# RP2350_QSPI.net
KiCad netlist of a schematic drawn in Altium Designer
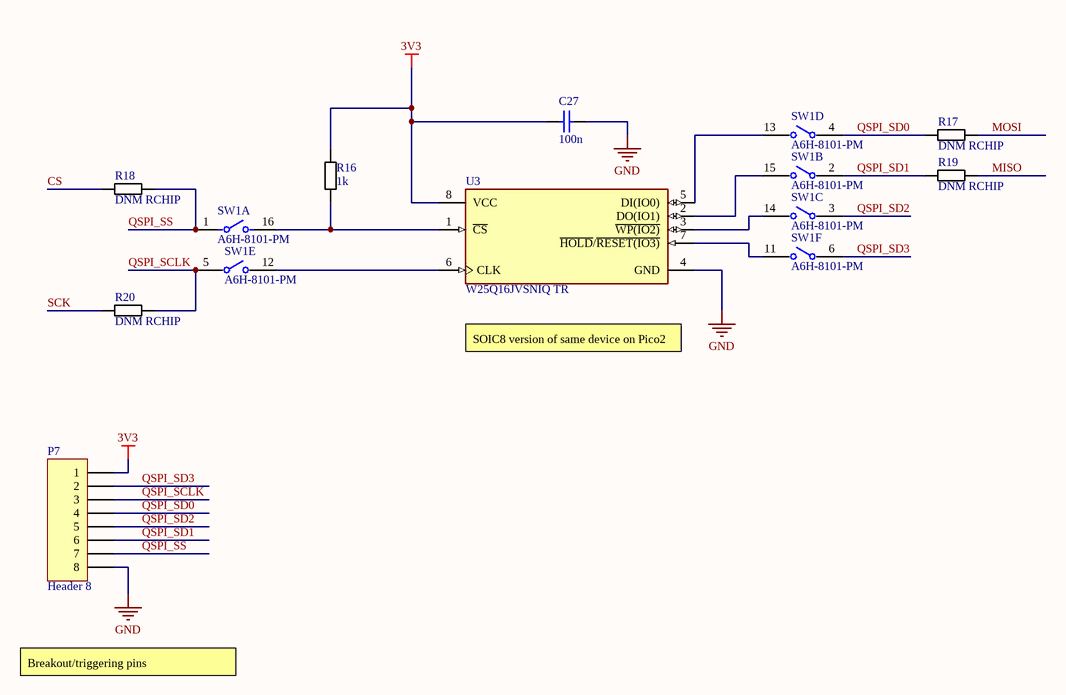
[diagram p0: RP2350_QSPI.SchDoc]

(export (version "E")
  (design (tool "Eeschema 10.0.6"))
  (components
    (comp (ref "C27")
      (value "100n")
      (footprint "CAPC0603_M")
      (description "100n, 0603")
      (fields (field (name "PART NUMBER") "CCHIP-100n-0603"))
      (libsource (lib "NewAE_AltiumLib") (part "CAP"))
    )
    (comp (ref "P7")
      (value "Header 8")
      (footprint "HDR1X8")
      (description "Header, 8-Pin")
      (fields (field (name "PUBLISHER") "Altium Limited"))
      (libsource (lib "Miscellaneous Connectors") (part "Header 8"))
    )
    (comp (ref "R16")
      (value "1k")
      (footprint "RESC1608X55N")
      (description "1k res, 0603, 1%, 1/10W")
      (fields (field (name "PART NUMBER") "RCHIP-1K-0603") (field (name "TOLERANCE") "1%"))
      (libsource (lib "") (part "RES-EU_1"))
    )
    (comp (ref "R17")
      (value "DNM RCHIP")
      (footprint "RESC1608X55N")
      (description "Do Not Mount Resistor")
      (fields (field (name "PART NUMBER") "RCHIP-DNM-0603"))
      (libsource (lib "NewAE_AltiumLib") (part "RES-EU"))
    )
    (comp (ref "R18")
      (value "DNM RCHIP")
      (footprint "RESC1608X55N")
      (description "Do Not Mount Resistor")
      (fields (field (name "PART NUMBER") "RCHIP-DNM-0603"))
      (libsource (lib "NewAE_AltiumLib") (part "RES-EU"))
    )
    (comp (ref "R19")
      (value "DNM RCHIP")
      (footprint "RESC1608X55N")
      (description "Do Not Mount Resistor")
      (fields (field (name "PART NUMBER") "RCHIP-DNM-0603"))
      (libsource (lib "NewAE_AltiumLib") (part "RES-EU"))
    )
    (comp (ref "R20")
      (value "DNM RCHIP")
      (footprint "RESC1608X55N")
      (description "Do Not Mount Resistor")
      (fields (field (name "PART NUMBER") "RCHIP-DNM-0603"))
      (libsource (lib "NewAE_AltiumLib") (part "RES-EU"))
    )
    (comp (ref "SW1")
      (value "A6H-8101-PM")
      (footprint "FP-A6H-8101-PM-MFG")
      (description "SWITCH SLIDE DIP SPST 25MA 24V")
      (libsource (lib "Altium Content Vault") (part "b1c630a2f26d6f55c46b66680387f8a"))
    )
    (comp (ref "U3")
      (value "W25Q16JVSNIQ TR")
      (footprint "FP-W25Q16JVSNIQ_TR-IPC_A")
      (description "IC FLASH 16MBIT SPI/QUAD 8SOIC")
      (libsource (lib "Altium Content Vault") (part "bca9062cdd4fd3591131373229c4e34"))
    )
  )
  (nets
    (net (code "1") (name "/CS") (class "Default")
      (node (ref "R18") (pin "1") (pinfunction "1_1") (pintype "passive"))
    )
    (net (code "2") (name "/MISO") (class "Default")
      (node (ref "R19") (pin "2") (pinfunction "2_2") (pintype "passive"))
    )
    (net (code "3") (name "/MOSI") (class "Default")
      (node (ref "R17") (pin "2") (pinfunction "2_2") (pintype "passive"))
    )
    (net (code "4") (name "/QSPI_SCLK") (class "Default")
      (node (ref "P7") (pin "3") (pinfunction "3_3") (pintype "passive"))
      (node (ref "R20") (pin "2") (pinfunction "2_2") (pintype "passive"))
      (node (ref "SW1") (pin "5") (pinfunction "5_5") (pintype "passive"))
    )
    (net (code "5") (name "/QSPI_SD0") (class "Default")
      (node (ref "P7") (pin "4") (pinfunction "4_4") (pintype "passive"))
      (node (ref "R17") (pin "1") (pinfunction "1_1") (pintype "passive"))
      (node (ref "SW1") (pin "4") (pinfunction "4_4") (pintype "passive"))
    )
    (net (code "6") (name "/QSPI_SD1") (class "Default")
      (node (ref "P7") (pin "6") (pinfunction "6_6") (pintype "passive"))
      (node (ref "R19") (pin "1") (pinfunction "1_1") (pintype "passive"))
      (node (ref "SW1") (pin "2") (pinfunction "2_2") (pintype "passive"))
    )
    (net (code "7") (name "/QSPI_SD2") (class "Default")
      (node (ref "P7") (pin "5") (pinfunction "5_5") (pintype "passive"))
      (node (ref "SW1") (pin "3") (pinfunction "3_3") (pintype "passive"))
    )
    (net (code "8") (name "/QSPI_SD3") (class "Default")
      (node (ref "P7") (pin "2") (pinfunction "2_2") (pintype "passive"))
      (node (ref "SW1") (pin "6") (pinfunction "6_6") (pintype "passive"))
    )
    (net (code "9") (name "/QSPI_SS") (class "Default")
      (node (ref "P7") (pin "7") (pinfunction "7_7") (pintype "passive"))
      (node (ref "R18") (pin "2") (pinfunction "2_2") (pintype "passive"))
      (node (ref "SW1") (pin "1") (pinfunction "1_1") (pintype "passive"))
    )
    (net (code "10") (name "/SCK") (class "Default")
      (node (ref "R20") (pin "1") (pinfunction "1_1") (pintype "passive"))
    )
    (net (code "11") (name "3V3") (class "Default")
      (node (ref "C27") (pin "1") (pinfunction "1_1") (pintype "passive"))
      (node (ref "P7") (pin "1") (pinfunction "1_1") (pintype "passive"))
      (node (ref "R16") (pin "1") (pinfunction "1_1") (pintype "passive"))
      (node (ref "U3") (pin "8") (pinfunction "VCC_8") (pintype "power_in"))
    )
    (net (code "12") (name "GND") (class "Default")
      (node (ref "C27") (pin "2") (pinfunction "2_2") (pintype "passive"))
      (node (ref "P7") (pin "8") (pinfunction "8_8") (pintype "passive"))
      (node (ref "U3") (pin "4") (pinfunction "GND_4") (pintype "power_in"))
    )
    (net (code "13") (name "Net-(U3-CLK)") (class "Default")
      (node (ref "SW1") (pin "12") (pinfunction "12_12") (pintype "passive"))
      (node (ref "U3") (pin "6") (pinfunction "CLK_6") (pintype "input"))
    )
    (net (code "14") (name "Net-(U3-DI(IO0))") (class "Default")
      (node (ref "SW1") (pin "13") (pinfunction "13_13") (pintype "passive"))
      (node (ref "U3") (pin "5") (pinfunction "DI(IO0)_5") (pintype "bidirectional"))
    )
    (net (code "15") (name "Net-(U3-DO(IO1))") (class "Default")
      (node (ref "SW1") (pin "15") (pinfunction "15_15") (pintype "passive"))
      (node (ref "U3") (pin "2") (pinfunction "DO(IO1)_2") (pintype "bidirectional"))
    )
    (net (code "16") (name "Net-(U3-~{CS})") (class "Default")
      (node (ref "R16") (pin "2") (pinfunction "2_2") (pintype "passive"))
      (node (ref "SW1") (pin "16") (pinfunction "16_16") (pintype "passive"))
      (node (ref "U3") (pin "1") (pinfunction "~{CS}_1") (pintype "input"))
    )
    (net (code "17") (name "Net-(U3-~{HOLD}{slash}~{RESET(IO3)})") (class "Default")
      (node (ref "SW1") (pin "11") (pinfunction "11_11") (pintype "passive"))
      (node (ref "U3") (pin "7") (pinfunction "~{HOLD}/~{RESET(IO3)}_7") (pintype "input"))
    )
    (net (code "18") (name "Net-(U3-~{WP(IO2)})") (class "Default")
      (node (ref "SW1") (pin "14") (pinfunction "14_14") (pintype "passive"))
      (node (ref "U3") (pin "3") (pinfunction "~{WP(IO2)}_3") (pintype "bidirectional"))
    )
  )
)
